# SMARTBALL_v1_2.net
KiCad netlist of a schematic drawn in EAGLE
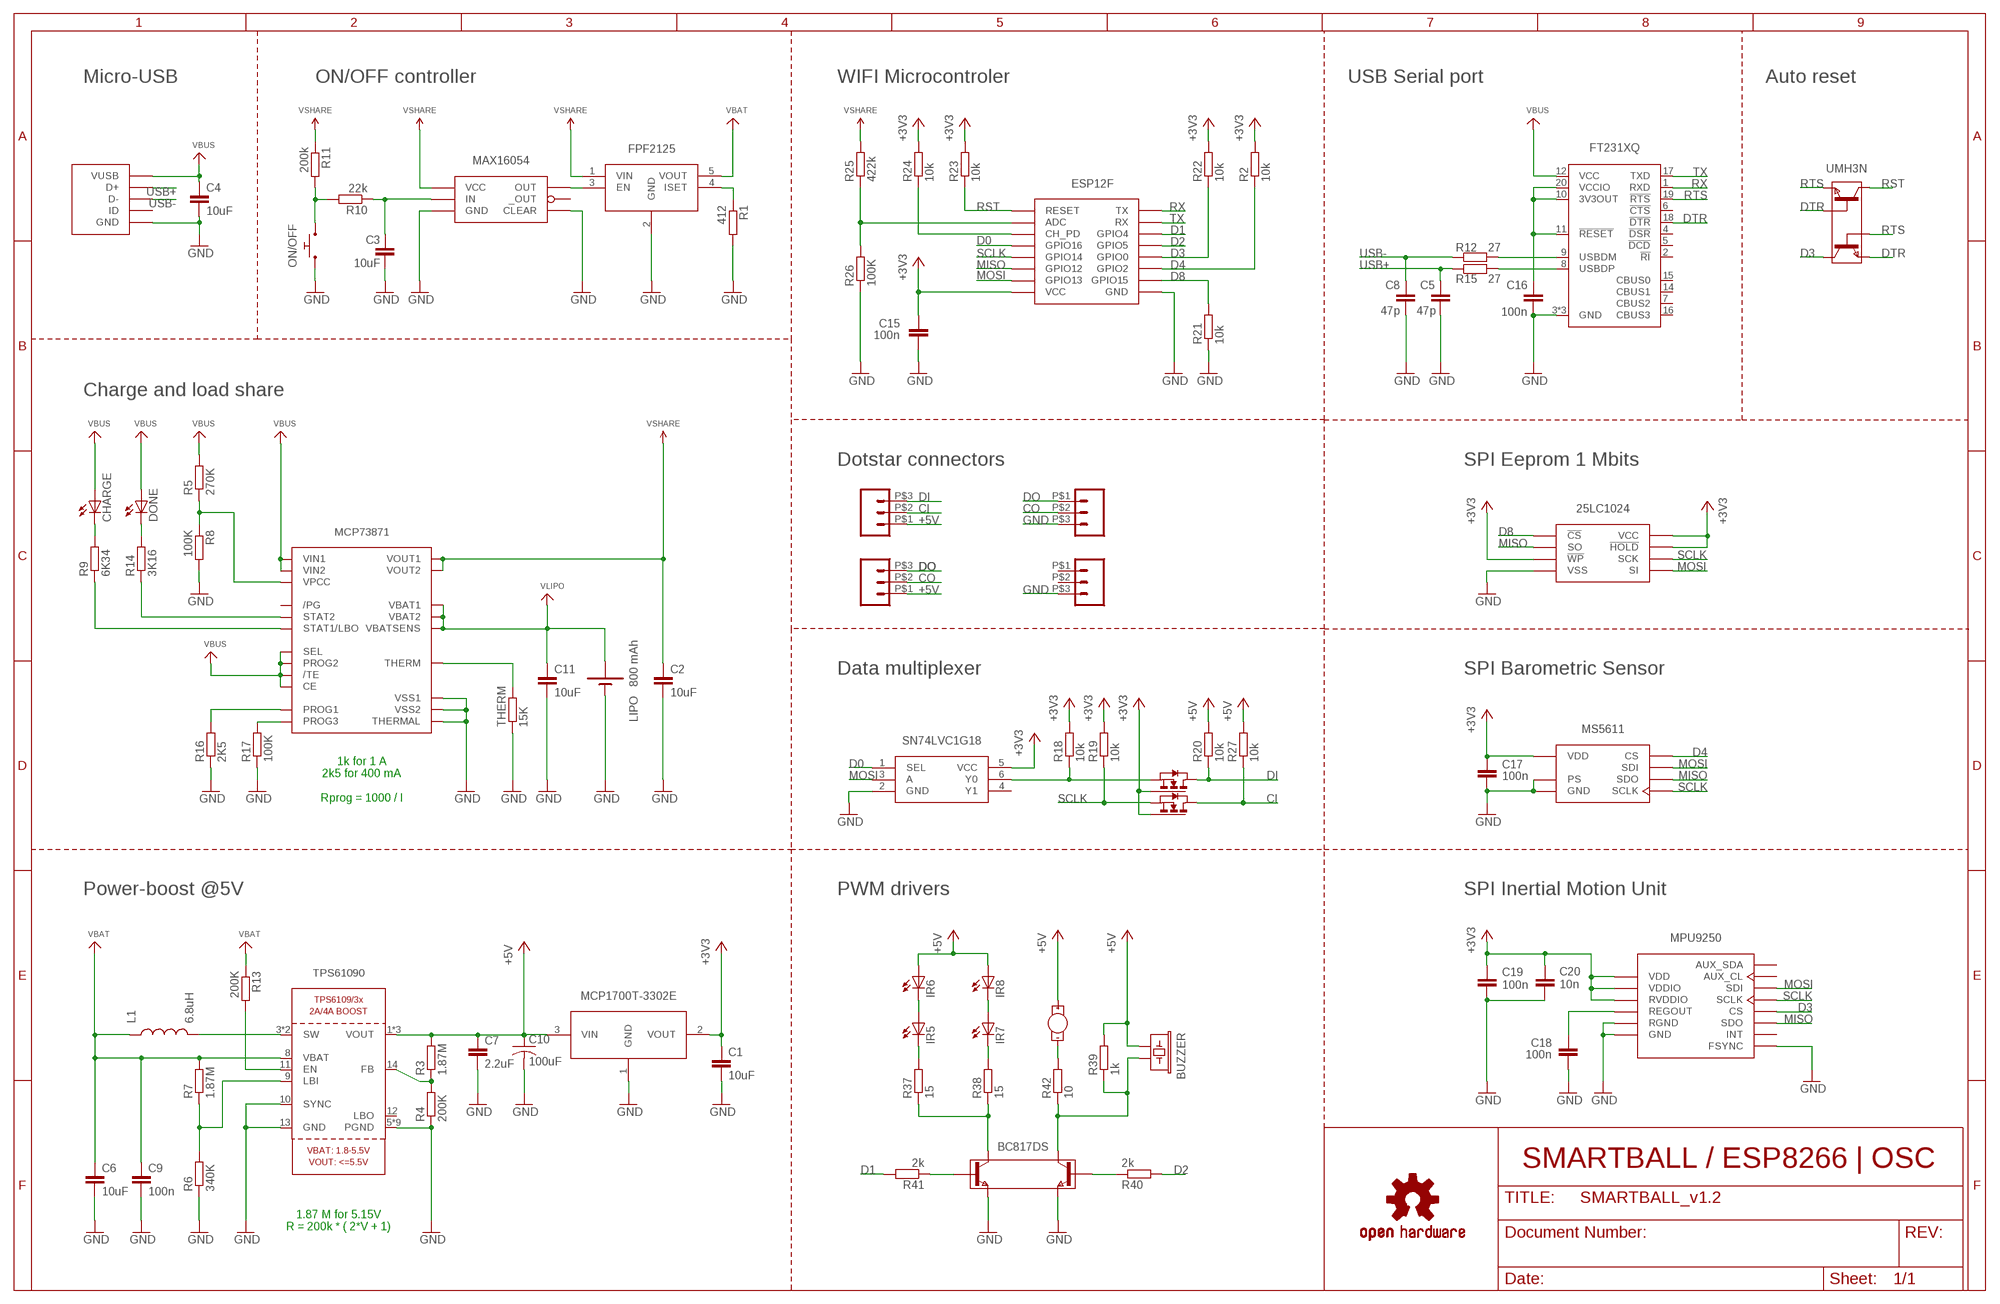
[diagram p0: schematic, sheet 1]

(export (version "E")
  (design (tool "Eeschema 10.0.6"))
  (components
    (comp (ref "BC817DS")
      (value "BC817DS")
      (footprint "eagle-import:SOT457R_PHILIPS")
      (libsource (lib "eagle-import") (part "BC817DS"))
    )
    (comp (ref "BUZZER")
      (value "BUZZER_PKMCS0909E4000-R1")
      (footprint "eagle-import:BUZZER_PKMCS0909E4000-R1")
      (libsource (lib "eagle-import") (part "BUZZER_PKMCS0909E4000-R1"))
    )
    (comp (ref "C1")
      (value "10uF")
      (footprint "eagle-import:C0603K")
      (libsource (lib "eagle-import") (part "C-EUC0603K"))
    )
    (comp (ref "C2")
      (value "10uF")
      (footprint "eagle-import:C0603K")
      (libsource (lib "eagle-import") (part "C-EUC0603K"))
    )
    (comp (ref "C3")
      (value "10uF")
      (footprint "eagle-import:C0603K")
      (libsource (lib "eagle-import") (part "C-EUC0603K"))
    )
    (comp (ref "C4")
      (value "10uF")
      (footprint "eagle-import:C0603K")
      (libsource (lib "eagle-import") (part "C-EUC0603K"))
    )
    (comp (ref "C5")
      (value "47p")
      (footprint "eagle-import:C0603K")
      (libsource (lib "eagle-import") (part "C-EUC0603K"))
    )
    (comp (ref "C6")
      (value "10uF")
      (footprint "eagle-import:C0603K")
      (libsource (lib "eagle-import") (part "C-EUC0603K"))
    )
    (comp (ref "C7")
      (value "2.2uF")
      (footprint "eagle-import:C0603K")
      (libsource (lib "eagle-import") (part "C-EUC0603K"))
    )
    (comp (ref "C8")
      (value "47p")
      (footprint "eagle-import:C0603K")
      (libsource (lib "eagle-import") (part "C-EUC0603K"))
    )
    (comp (ref "C9")
      (value "100n")
      (footprint "eagle-import:C0603K")
      (libsource (lib "eagle-import") (part "C-EUC0603K"))
    )
    (comp (ref "C10")
      (value "100uF")
      (footprint "eagle-import:C1210")
      (libsource (lib "eagle-import") (part "C-USC1210"))
    )
    (comp (ref "C11")
      (value "10uF")
      (footprint "eagle-import:C0603K")
      (libsource (lib "eagle-import") (part "C-EUC0603K"))
    )
    (comp (ref "C15")
      (value "100n")
      (footprint "eagle-import:C0603K")
      (libsource (lib "eagle-import") (part "C-EUC0603K"))
    )
    (comp (ref "C16")
      (value "100n")
      (footprint "eagle-import:C0603K")
      (libsource (lib "eagle-import") (part "C-EUC0603K"))
    )
    (comp (ref "C17")
      (value "100n")
      (footprint "eagle-import:C0603K")
      (libsource (lib "eagle-import") (part "C-EUC0603K"))
    )
    (comp (ref "C18")
      (value "100n")
      (footprint "eagle-import:C0603K")
      (libsource (lib "eagle-import") (part "C-EUC0603K"))
    )
    (comp (ref "C19")
      (value "100n")
      (footprint "eagle-import:C0603K")
      (libsource (lib "eagle-import") (part "C-EUC0603K"))
    )
    (comp (ref "C20")
      (value "10n")
      (footprint "eagle-import:C0603K")
      (libsource (lib "eagle-import") (part "C-EUC0603K"))
    )
    (comp (ref "CHARGE")
      (value "KINGBRIGHT_16X08")
      (footprint "eagle-import:KINGBRIGHT_16X08")
      (libsource (lib "eagle-import") (part "KINGBRIGHT_16X08"))
    )
    (comp (ref "DONE")
      (value "KINGBRIGHT_16X08")
      (footprint "eagle-import:KINGBRIGHT_16X08")
      (libsource (lib "eagle-import") (part "KINGBRIGHT_16X08"))
    )
    (comp (ref "ESP12F")
      (value "ESP12")
      (footprint "eagle-import:ESP12")
      (libsource (lib "eagle-import") (part "ESP12"))
    )
    (comp (ref "FT231XQ")
      (value "FT231X")
      (footprint "eagle-import:QFN20")
      (libsource (lib "eagle-import") (part "FT231X"))
    )
    (comp (ref "IR5")
      (value "LED-SFH4050")
      (footprint "eagle-import:SFH4050")
      (libsource (lib "eagle-import") (part "LED-SFH4050"))
    )
    (comp (ref "IR6")
      (value "LED-SFH4050")
      (footprint "eagle-import:SFH4050")
      (libsource (lib "eagle-import") (part "LED-SFH4050"))
    )
    (comp (ref "IR7")
      (value "LED-SFH4050")
      (footprint "eagle-import:SFH4050")
      (libsource (lib "eagle-import") (part "LED-SFH4050"))
    )
    (comp (ref "IR8")
      (value "LED-SFH4050")
      (footprint "eagle-import:SFH4050")
      (libsource (lib "eagle-import") (part "LED-SFH4050"))
    )
    (comp (ref "L1")
      (value "6.8uH")
      (footprint "eagle-import:ASPIAIG-S4035")
      (libsource (lib "eagle-import") (part "ASPIAIG-S4035"))
    )
    (comp (ref "LIPO")
      (value "BATTERY_CONNECTOR")
      (footprint "eagle-import:MOTOR_CONNECTOR")
      (libsource (lib "eagle-import") (part "BATTERY_CONNECTOR"))
    )
    (comp (ref "LOGO1")
      (value "OSHW-LOGOL")
      (footprint "eagle-import:OSHW-LOGO-L")
      (libsource (lib "eagle-import") (part "OSHW-LOGOL"))
    )
    (comp (ref "MCP73871")
      (value "MCP73871")
      (footprint "eagle-import:QFN20_4MM")
      (libsource (lib "eagle-import") (part "MCP73871"))
    )
    (comp (ref "MOTOR")
      (value "MOTOR_CONNECTOR")
      (footprint "eagle-import:MOTOR_CONNECTOR")
      (libsource (lib "eagle-import") (part "MOTOR_CONNECTOR"))
    )
    (comp (ref "ON/OFF")
      (value "B3U-3000P-B")
      (footprint "eagle-import:B3U-3000P-B")
      (libsource (lib "eagle-import") (part "B3U-3000P-B"))
    )
    (comp (ref "R1")
      (value "412")
      (footprint "eagle-import:R0402")
      (libsource (lib "eagle-import") (part "R-EU_R0402"))
    )
    (comp (ref "R2")
      (value "10k")
      (footprint "eagle-import:R0402")
      (libsource (lib "eagle-import") (part "R-EU_R0402"))
    )
    (comp (ref "R3")
      (value "1.87M")
      (footprint "eagle-import:R0402")
      (libsource (lib "eagle-import") (part "R-EU_R0402"))
    )
    (comp (ref "R4")
      (value "200K")
      (footprint "eagle-import:R0402")
      (libsource (lib "eagle-import") (part "R-EU_R0402"))
    )
    (comp (ref "R5")
      (value "270K")
      (footprint "eagle-import:R0402")
      (libsource (lib "eagle-import") (part "R-EU_R0402"))
    )
    (comp (ref "R6")
      (value "340K")
      (footprint "eagle-import:R0402")
      (libsource (lib "eagle-import") (part "R-EU_R0402"))
    )
    (comp (ref "R7")
      (value "1.87M")
      (footprint "eagle-import:R0402")
      (libsource (lib "eagle-import") (part "R-EU_R0402"))
    )
    (comp (ref "R8")
      (value "100K")
      (footprint "eagle-import:R0402")
      (libsource (lib "eagle-import") (part "R-EU_R0402"))
    )
    (comp (ref "R9")
      (value "6K34")
      (footprint "eagle-import:R0402")
      (libsource (lib "eagle-import") (part "R-EU_R0402"))
    )
    (comp (ref "R10")
      (value "22k")
      (footprint "eagle-import:R0402")
      (libsource (lib "eagle-import") (part "R-EU_R0402"))
    )
    (comp (ref "R11")
      (value "200k")
      (footprint "eagle-import:R0402")
      (libsource (lib "eagle-import") (part "R-EU_R0402"))
    )
    (comp (ref "R12")
      (value "27")
      (footprint "eagle-import:R0402")
      (libsource (lib "eagle-import") (part "R-EU_R0402"))
    )
    (comp (ref "R13")
      (value "200K")
      (footprint "eagle-import:R0402")
      (libsource (lib "eagle-import") (part "R-EU_R0402"))
    )
    (comp (ref "R14")
      (value "3K16")
      (footprint "eagle-import:R0402")
      (libsource (lib "eagle-import") (part "R-EU_R0402"))
    )
    (comp (ref "R15")
      (value "27")
      (footprint "eagle-import:R0402")
      (libsource (lib "eagle-import") (part "R-EU_R0402"))
    )
    (comp (ref "R16")
      (value "2K5")
      (footprint "eagle-import:R0402")
      (libsource (lib "eagle-import") (part "R-EU_R0402"))
    )
    (comp (ref "R17")
      (value "100K")
      (footprint "eagle-import:R0402")
      (libsource (lib "eagle-import") (part "R-EU_R0402"))
    )
    (comp (ref "R18")
      (value "10k")
      (footprint "eagle-import:R0402")
      (libsource (lib "eagle-import") (part "R-EU_R0402"))
    )
    (comp (ref "R19")
      (value "10k")
      (footprint "eagle-import:R0402")
      (libsource (lib "eagle-import") (part "R-EU_R0402"))
    )
    (comp (ref "R20")
      (value "10k")
      (footprint "eagle-import:R0402")
      (libsource (lib "eagle-import") (part "R-EU_R0402"))
    )
    (comp (ref "R21")
      (value "10k")
      (footprint "eagle-import:R0402")
      (libsource (lib "eagle-import") (part "R-EU_R0402"))
    )
    (comp (ref "R22")
      (value "10k")
      (footprint "eagle-import:R0402")
      (libsource (lib "eagle-import") (part "R-EU_R0402"))
    )
    (comp (ref "R23")
      (value "10k")
      (footprint "eagle-import:R0402")
      (libsource (lib "eagle-import") (part "R-EU_R0402"))
    )
    (comp (ref "R24")
      (value "10k")
      (footprint "eagle-import:R0402")
      (libsource (lib "eagle-import") (part "R-EU_R0402"))
    )
    (comp (ref "R25")
      (value "422k")
      (footprint "eagle-import:R0402")
      (libsource (lib "eagle-import") (part "R-EU_R0402"))
    )
    (comp (ref "R26")
      (value "100K")
      (footprint "eagle-import:R0402")
      (libsource (lib "eagle-import") (part "R-EU_R0402"))
    )
    (comp (ref "R27")
      (value "10k")
      (footprint "eagle-import:R0402")
      (libsource (lib "eagle-import") (part "R-EU_R0402"))
    )
    (comp (ref "R37")
      (value "15")
      (footprint "eagle-import:R0402")
      (libsource (lib "eagle-import") (part "R-EU_R0402"))
    )
    (comp (ref "R38")
      (value "15")
      (footprint "eagle-import:R0402")
      (libsource (lib "eagle-import") (part "R-EU_R0402"))
    )
    (comp (ref "R39")
      (value "1k")
      (footprint "eagle-import:R0402")
      (libsource (lib "eagle-import") (part "R-EU_R0402"))
    )
    (comp (ref "R40")
      (value "2k")
      (footprint "eagle-import:R0402")
      (libsource (lib "eagle-import") (part "R-EU_R0402"))
    )
    (comp (ref "R41")
      (value "2k")
      (footprint "eagle-import:R0402")
      (libsource (lib "eagle-import") (part "R-EU_R0402"))
    )
    (comp (ref "R42")
      (value "10")
      (footprint "eagle-import:R0402")
      (libsource (lib "eagle-import") (part "R-EU_R0402"))
    )
    (comp (ref "THERM")
      (value "15K")
      (footprint "eagle-import:R0402")
      (libsource (lib "eagle-import") (part "R-EU_R0402"))
    )
    (comp (ref "TPS61090")
      (value "TPS61090RSAR")
      (footprint "eagle-import:PVQFN-16")
      (libsource (lib "eagle-import") (part "VREG_TPS6103X"))
    )
    (comp (ref "U$1")
      (value "MOLEX-USB")
      (footprint "eagle-import:MOLEX-USB")
      (libsource (lib "eagle-import") (part "MOLEX-USB"))
    )
    (comp (ref "U$2")
      (value "FPF2125")
      (footprint "eagle-import:SOT23-5")
      (libsource (lib "eagle-import") (part "FPF2125"))
    )
    (comp (ref "U$3")
      (value "MCP1700T")
      (footprint "eagle-import:SOT23-3")
      (libsource (lib "eagle-import") (part "MCP1700T"))
    )
    (comp (ref "U$5")
      (value "CONN_03_SMD")
      (footprint "eagle-import:CONN03_SMD")
      (libsource (lib "eagle-import") (part "CONN_03_SMD"))
    )
    (comp (ref "U$6")
      (value "CONN_03_SMD")
      (footprint "eagle-import:CONN03_SMD")
      (libsource (lib "eagle-import") (part "CONN_03_SMD"))
    )
    (comp (ref "U$12")
      (value "MAX16054")
      (footprint "eagle-import:TSOT23-6")
      (libsource (lib "eagle-import") (part "MAX16054"))
    )
    (comp (ref "U$14")
      (value "CONN_03_SMD")
      (footprint "eagle-import:CONN03_SMD")
      (libsource (lib "eagle-import") (part "CONN_03_SMD"))
    )
    (comp (ref "U$15")
      (value "CONN_03_SMD")
      (footprint "eagle-import:CONN03_SMD")
      (libsource (lib "eagle-import") (part "CONN_03_SMD"))
    )
    (comp (ref "U$16")
      (value "25LC1024DFN-S")
      (footprint "eagle-import:DFN-S")
      (libsource (lib "eagle-import") (part "25LC1024DFN-S"))
    )
    (comp (ref "U$17")
      (value "MS5611")
      (footprint "eagle-import:MS5611-QFN")
      (libsource (lib "eagle-import") (part "MS5611"))
    )
    (comp (ref "U$20")
      (value "SN74LVC1G18")
      (footprint "eagle-import:DCK_R-PDSO-G6")
      (libsource (lib "eagle-import") (part "SN74LVC1G18"))
    )
    (comp (ref "U$21")
      (value "MPU-9250QFN24G")
      (footprint "eagle-import:QFN24G-0.4-3X3MM")
      (libsource (lib "eagle-import") (part "MPU-9250QFN24G"))
    )
    (comp (ref "U$22")
      (value "2N7002PS")
      (footprint "eagle-import:SOT363_PHILIPS")
      (libsource (lib "eagle-import") (part "2N7002PS"))
    )
    (comp (ref "UMH3N")
      (value "UMH3N")
      (footprint "eagle-import:SOT363_PHILIPS")
      (libsource (lib "eagle-import") (part "UMH3N"))
    )
  )
  (nets
    (net (code "1") (name "+3V3") (class "Default")
      (node (ref "C1") (pin "1") (pinfunction "1_1") (pintype "passive"))
      (node (ref "C15") (pin "1") (pinfunction "1_1") (pintype "passive"))
      (node (ref "C17") (pin "1") (pinfunction "1_1") (pintype "passive"))
      (node (ref "C19") (pin "1") (pinfunction "1_1") (pintype "passive"))
      (node (ref "C20") (pin "2") (pinfunction "2_2") (pintype "passive"))
      (node (ref "ESP12F") (pin "VCC") (pinfunction "VCC_VCC") (pintype "bidirectional"))
      (node (ref "R18") (pin "2") (pinfunction "2_2") (pintype "passive"))
      (node (ref "R19") (pin "2") (pinfunction "2_2") (pintype "passive"))
      (node (ref "R2") (pin "2") (pinfunction "2_2") (pintype "passive"))
      (node (ref "R22") (pin "2") (pinfunction "2_2") (pintype "passive"))
      (node (ref "R23") (pin "2") (pinfunction "2_2") (pintype "passive"))
      (node (ref "R24") (pin "2") (pinfunction "2_2") (pintype "passive"))
      (node (ref "U$16") (pin "3") (pinfunction "~{WP}_3") (pintype "bidirectional"))
      (node (ref "U$16") (pin "7") (pinfunction "~{HOLD}_7") (pintype "bidirectional"))
      (node (ref "U$16") (pin "8") (pinfunction "VCC_8") (pintype "bidirectional"))
      (node (ref "U$17") (pin "P$1") (pinfunction "VDD_P$1") (pintype "power_in"))
      (node (ref "U$20") (pin "5") (pinfunction "VCC_5") (pintype "bidirectional"))
      (node (ref "U$21") (pin "1") (pinfunction "RVDDIO_1") (pintype "bidirectional"))
      (node (ref "U$21") (pin "13") (pinfunction "VDD_13") (pintype "bidirectional"))
      (node (ref "U$21") (pin "8") (pinfunction "VDDIO_8") (pintype "bidirectional"))
      (node (ref "U$22") (pin "2") (pinfunction "G1_2") (pintype "passive"))
      (node (ref "U$22") (pin "5") (pinfunction "G2_5") (pintype "passive"))
      (node (ref "U$3") (pin "2") (pinfunction "VOUT_2") (pintype "bidirectional"))
    )
    (net (code "2") (name "+5V") (class "Default")
      (node (ref "BUZZER") (pin "P$1") (pinfunction "1_P$1") (pintype "passive"))
      (node (ref "C10") (pin "1") (pinfunction "1_1") (pintype "passive"))
      (node (ref "C7") (pin "1") (pinfunction "1_1") (pintype "passive"))
      (node (ref "IR6") (pin "P$1") (pinfunction "A_P$1") (pintype "passive"))
      (node (ref "IR8") (pin "P$1") (pinfunction "A_P$1") (pintype "passive"))
      (node (ref "MOTOR") (pin "+") (pinfunction "+_+") (pintype "bidirectional"))
      (node (ref "R20") (pin "2") (pinfunction "2_2") (pintype "passive"))
      (node (ref "R27") (pin "2") (pinfunction "2_2") (pintype "passive"))
      (node (ref "R3") (pin "2") (pinfunction "2_2") (pintype "passive"))
      (node (ref "R39") (pin "2") (pinfunction "2_2") (pintype "passive"))
      (node (ref "TPS61090") (pin "1") (pinfunction "VOUT_1") (pintype "power_in"))
      (node (ref "TPS61090") (pin "15") (pinfunction "VOUT_15") (pintype "power_in"))
      (node (ref "TPS61090") (pin "16") (pinfunction "VOUT_16") (pintype "power_in"))
      (node (ref "U$15") (pin "P$1") (pinfunction "1_P$1") (pintype "passive"))
      (node (ref "U$3") (pin "3") (pinfunction "VIN_3") (pintype "bidirectional"))
      (node (ref "U$5") (pin "P$1") (pinfunction "1_P$1") (pintype "passive"))
    )
    (net (code "3") (name "/CI") (class "Default")
      (node (ref "R27") (pin "1") (pinfunction "1_1") (pintype "passive"))
      (node (ref "U$22") (pin "3") (pinfunction "D2_3") (pintype "passive"))
      (node (ref "U$5") (pin "P$2") (pinfunction "2_P$2") (pintype "passive"))
    )
    (net (code "4") (name "/CO") (class "Default")
      (node (ref "U$15") (pin "P$2") (pinfunction "2_P$2") (pintype "passive"))
      (node (ref "U$6") (pin "P$2") (pinfunction "2_P$2") (pintype "passive"))
    )
    (net (code "5") (name "/D0") (class "Default")
      (node (ref "ESP12F") (pin "GPIO16") (pinfunction "GPIO16_GPIO16") (pintype "bidirectional"))
      (node (ref "U$20") (pin "1") (pinfunction "SEL_1") (pintype "bidirectional"))
    )
    (net (code "6") (name "/D1") (class "Default")
      (node (ref "ESP12F") (pin "GPIO4") (pinfunction "GPIO4_GPIO4") (pintype "bidirectional"))
      (node (ref "R41") (pin "2") (pinfunction "2_2") (pintype "passive"))
    )
    (net (code "7") (name "/D2") (class "Default")
      (node (ref "ESP12F") (pin "GPIO5") (pinfunction "GPIO5_GPIO5") (pintype "bidirectional"))
      (node (ref "R40") (pin "2") (pinfunction "2_2") (pintype "passive"))
    )
    (net (code "8") (name "/D3") (class "Default")
      (node (ref "ESP12F") (pin "GPIO0") (pinfunction "GPIO0_GPIO0") (pintype "bidirectional"))
      (node (ref "R22") (pin "1") (pinfunction "1_1") (pintype "passive"))
      (node (ref "U$21") (pin "22") (pinfunction "CS_22") (pintype "bidirectional"))
      (node (ref "UMH3N") (pin "3") (pinfunction "C2_3") (pintype "passive"))
    )
    (net (code "9") (name "/D4") (class "Default")
      (node (ref "ESP12F") (pin "GPIO2") (pinfunction "GPIO2_GPIO2") (pintype "bidirectional"))
      (node (ref "R2") (pin "1") (pinfunction "1_1") (pintype "passive"))
      (node (ref "U$17") (pin "P$4") (pinfunction "CS_P$4") (pintype "bidirectional"))
      (node (ref "U$17") (pin "P$5") (pinfunction "CS_P$5") (pintype "bidirectional"))
    )
    (net (code "10") (name "/D8") (class "Default")
      (node (ref "ESP12F") (pin "GPIO15") (pinfunction "GPIO15_GPIO15") (pintype "bidirectional"))
      (node (ref "R21") (pin "2") (pinfunction "2_2") (pintype "passive"))
      (node (ref "U$16") (pin "1") (pinfunction "~{CS}_1") (pintype "bidirectional"))
    )
    (net (code "11") (name "/DI") (class "Default")
      (node (ref "R20") (pin "1") (pinfunction "1_1") (pintype "passive"))
      (node (ref "U$22") (pin "6") (pinfunction "D1_6") (pintype "passive"))
      (node (ref "U$5") (pin "P$3") (pinfunction "3_P$3") (pintype "passive"))
    )
    (net (code "12") (name "/DO") (class "Default")
      (node (ref "U$15") (pin "P$3") (pinfunction "3_P$3") (pintype "passive"))
      (node (ref "U$6") (pin "P$1") (pinfunction "1_P$1") (pintype "passive"))
    )
    (net (code "13") (name "/DTR") (class "Default")
      (node (ref "FT231XQ") (pin "18") (pinfunction "~{DTR}_18") (pintype "bidirectional"))
      (node (ref "UMH3N") (pin "2") (pinfunction "B1_2") (pintype "passive"))
      (node (ref "UMH3N") (pin "4") (pinfunction "E2_4") (pintype "passive"))
    )
    (net (code "14") (name "/MISO") (class "Default")
      (node (ref "ESP12F") (pin "GPIO12") (pinfunction "GPIO12_GPIO12") (pintype "bidirectional"))
      (node (ref "U$16") (pin "2") (pinfunction "SO_2") (pintype "bidirectional"))
      (node (ref "U$17") (pin "P$6") (pinfunction "SDO_P$6") (pintype "output"))
      (node (ref "U$21") (pin "9") (pinfunction "SDO_9") (pintype "bidirectional"))
    )
    (net (code "15") (name "/MOSI") (class "Default")
      (node (ref "ESP12F") (pin "GPIO13") (pinfunction "GPIO13_GPIO13") (pintype "bidirectional"))
      (node (ref "U$16") (pin "5") (pinfunction "SI_5") (pintype "bidirectional"))
      (node (ref "U$17") (pin "P$7") (pinfunction "SDI_P$7") (pintype "input"))
      (node (ref "U$20") (pin "3") (pinfunction "A_3") (pintype "bidirectional"))
      (node (ref "U$21") (pin "24") (pinfunction "SDI_24") (pintype "bidirectional"))
    )
    (net (code "16") (name "/RST") (class "Default")
      (node (ref "ESP12F") (pin "RESET") (pinfunction "RESET_RESET") (pintype "bidirectional"))
      (node (ref "R23") (pin "1") (pinfunction "1_1") (pintype "passive"))
      (node (ref "UMH3N") (pin "6") (pinfunction "C1_6") (pintype "passive"))
    )
    (net (code "17") (name "/RTS") (class "Default")
      (node (ref "FT231XQ") (pin "19") (pinfunction "~{RTS}_19") (pintype "bidirectional"))
      (node (ref "UMH3N") (pin "1") (pinfunction "E1_1") (pintype "passive"))
      (node (ref "UMH3N") (pin "5") (pinfunction "B2_5") (pintype "passive"))
    )
    (net (code "18") (name "/RX") (class "Default")
      (node (ref "ESP12F") (pin "TX") (pinfunction "TX_TX") (pintype "bidirectional"))
      (node (ref "FT231XQ") (pin "1") (pinfunction "RXD_1") (pintype "bidirectional"))
    )
    (net (code "19") (name "/SCLK") (class "Default")
      (node (ref "ESP12F") (pin "GPIO14") (pinfunction "GPIO14_GPIO14") (pintype "bidirectional"))
      (node (ref "R19") (pin "1") (pinfunction "1_1") (pintype "passive"))
      (node (ref "U$16") (pin "6") (pinfunction "SCK_6") (pintype "bidirectional"))
      (node (ref "U$17") (pin "P$8") (pinfunction "SCLK_P$8") (pintype "input"))
      (node (ref "U$21") (pin "23") (pinfunction "SCLK_23") (pintype "bidirectional"))
      (node (ref "U$22") (pin "4") (pinfunction "S2_4") (pintype "passive"))
    )
    (net (code "20") (name "/TX") (class "Default")
      (node (ref "ESP12F") (pin "RX") (pinfunction "RX_RX") (pintype "bidirectional"))
      (node (ref "FT231XQ") (pin "17") (pinfunction "TXD_17") (pintype "bidirectional"))
    )
    (net (code "21") (name "/USB+") (class "Default")
      (node (ref "C5") (pin "1") (pinfunction "1_1") (pintype "passive"))
      (node (ref "R15") (pin "1") (pinfunction "1_1") (pintype "passive"))
      (node (ref "U$1") (pin "D+") (pinfunction "D+_D+") (pintype "bidirectional"))
    )
    (net (code "22") (name "/USB-") (class "Default")
      (node (ref "C8") (pin "1") (pinfunction "1_1") (pintype "passive"))
      (node (ref "R12") (pin "1") (pinfunction "1_1") (pintype "passive"))
      (node (ref "U$1") (pin "D-") (pinfunction "D-_D-") (pintype "bidirectional"))
    )
    (net (code "23") (name "GND") (class "Default")
      (node (ref "BC817DS") (pin "1") (pinfunction "E1_1") (pintype "passive"))
      (node (ref "BC817DS") (pin "4") (pinfunction "E2_4") (pintype "passive"))
      (node (ref "C1") (pin "2") (pinfunction "2_2") (pintype "passive"))
      (node (ref "C10") (pin "2") (pinfunction "2_2") (pintype "passive"))
      (node (ref "C11") (pin "2") (pinfunction "2_2") (pintype "passive"))
      (node (ref "C15") (pin "2") (pinfunction "2_2") (pintype "passive"))
      (node (ref "C16") (pin "2") (pinfunction "2_2") (pintype "passive"))
      (node (ref "C17") (pin "2") (pinfunction "2_2") (pintype "passive"))
      (node (ref "C18") (pin "2") (pinfunction "2_2") (pintype "passive"))
      (node (ref "C19") (pin "2") (pinfunction "2_2") (pintype "passive"))
      (node (ref "C2") (pin "2") (pinfunction "2_2") (pintype "passive"))
      (node (ref "C20") (pin "1") (pinfunction "1_1") (pintype "passive"))
      (node (ref "C3") (pin "2") (pinfunction "2_2") (pintype "passive"))
      (node (ref "C4") (pin "2") (pinfunction "2_2") (pintype "passive"))
      (node (ref "C5") (pin "2") (pinfunction "2_2") (pintype "passive"))
      (node (ref "C6") (pin "2") (pinfunction "2_2") (pintype "passive"))
      (node (ref "C7") (pin "2") (pinfunction "2_2") (pintype "passive"))
      (node (ref "C8") (pin "2") (pinfunction "2_2") (pintype "passive"))
      (node (ref "C9") (pin "2") (pinfunction "2_2") (pintype "passive"))
      (node (ref "ESP12F") (pin "GND") (pinfunction "GND_GND") (pintype "bidirectional"))
      (node (ref "FT231XQ") (pin "13") (pinfunction "GND_13") (pintype "bidirectional"))
      (node (ref "FT231XQ") (pin "3") (pinfunction "GND_3") (pintype "bidirectional"))
      (node (ref "FT231XQ") (pin "EXP") (pinfunction "GND_EXP") (pintype "bidirectional"))
      (node (ref "LIPO") (pin "-") (pinfunction "-_-") (pintype "power_in"))
      (node (ref "MCP73871") (pin "P$10") (pinfunction "VSS1_P$10") (pintype "bidirectional"))
      (node (ref "MCP73871") (pin "P$11") (pinfunction "VSS2_P$11") (pintype "bidirectional"))
      (node (ref "MCP73871") (pin "P$21") (pinfunction "THERMAL_P$21") (pintype "bidirectional"))
      (node (ref "ON/OFF") (pin "P$1") (pinfunction "1_P$1") (pintype "passive"))
      (node (ref "R1") (pin "2") (pinfunction "2_2") (pintype "passive"))
      (node (ref "R16") (pin "1") (pinfunction "1_1") (pintype "passive"))
      (node (ref "R17") (pin "1") (pinfunction "1_1") (pintype "passive"))
      (node (ref "R21") (pin "1") (pinfunction "1_1") (pintype "passive"))
      (node (ref "R26") (pin "1") (pinfunction "1_1") (pintype "passive"))
      (node (ref "R4") (pin "1") (pinfunction "1_1") (pintype "passive"))
      (node (ref "R6") (pin "1") (pinfunction "1_1") (pintype "passive"))
      (node (ref "R8") (pin "2") (pinfunction "2_2") (pintype "passive"))
      (node (ref "THERM") (pin "1") (pinfunction "1_1") (pintype "passive"))
      (node (ref "TPS61090") (pin "10") (pinfunction "SYNC_10") (pintype "input"))
      (node (ref "TPS61090") (pin "13") (pinfunction "GND_13") (pintype "power_in"))
      (node (ref "TPS61090") (pin "5") (pinfunction "PGND_5") (pintype "power_in"))
      (node (ref "TPS61090") (pin "6") (pinfunction "PGND_6") (pintype "power_in"))
      (node (ref "TPS61090") (pin "7") (pinfunction "PGND_7") (pintype "power_in"))
      (node (ref "TPS61090") (pin "P$18") (pinfunction "PGND_P$18") (pintype "power_in"))
      (node (ref "TPS61090") (pin "P$19") (pinfunction "PGND_P$19") (pintype "power_in"))
      (node (ref "TPS61090") (pin "P$20") (pinfunction "PGND_P$20") (pintype "power_in"))
      (node (ref "TPS61090") (pin "P$21") (pinfunction "PGND_P$21") (pintype "power_in"))
      (node (ref "TPS61090") (pin "P$22") (pinfunction "PGND_P$22") (pintype "power_in"))
      (node (ref "TPS61090") (pin "THERMAL") (pinfunction "PGND_THERMAL") (pintype "power_in"))
      (node (ref "U$1") (pin "GND") (pinfunction "GND_GND") (pintype "bidirectional"))
      (node (ref "U$1") (pin "P$1") (pinfunction "GND_P$1") (pintype "bidirectional"))
      (node (ref "U$1") (pin "P$11") (pinfunction "GND_P$11") (pintype "bidirectional"))
      (node (ref "U$1") (pin "SHELL1") (pinfunction "GND_SHELL1") (pintype "bidirectional"))
      (node (ref "U$1") (pin "SHELL2") (pinfunction "GND_SHELL2") (pintype "bidirectional"))
      (node (ref "U$1") (pin "SHELL5") (pinfunction "GND_SHELL5") (pintype "bidirectional"))
      (node (ref "U$1") (pin "SHELL6") (pinfunction "GND_SHELL6") (pintype "bidirectional"))
      (node (ref "U$12") (pin "CLEAR") (pinfunction "CLEAR_CLEAR") (pintype "bidirectional"))
      (node (ref "U$12") (pin "GND") (pinfunction "GND_GND") (pintype "bidirectional"))
      (node (ref "U$14") (pin "P$3") (pinfunction "3_P$3") (pintype "passive"))
      (node (ref "U$16") (pin "4") (pinfunction "VSS_4") (pintype "bidirectional"))
      (node (ref "U$17") (pin "P$2") (pinfunction "PS_P$2") (pintype "input"))
      (node (ref "U$17") (pin "P$3") (pinfunction "GND_P$3") (pintype "power_in"))
      (node (ref "U$2") (pin "2") (pinfunction "GND_2") (pintype "bidirectional"))
      (node (ref "U$20") (pin "2") (pinfunction "GND_2") (pintype "bidirectional"))
      (node (ref "U$21") (pin "11") (pinfunction "FSYNC_11") (pintype "bidirectional"))
      (node (ref "U$21") (pin "18") (pinfunction "GND_18") (pintype "bidirectional"))
      (node (ref "U$21") (pin "20") (pinfunction "RGND_20") (pintype "bidirectional"))
      (node (ref "U$3") (pin "1") (pinfunction "GND_1") (pintype "bidirectional"))
      (node (ref "U$6") (pin "P$3") (pinfunction "3_P$3") (pintype "passive"))
    )
    (net (code "24") (name "Net-(BC817DS-B1)") (class "Default")
      (node (ref "BC817DS") (pin "2") (pinfunction "B1_2") (pintype "passive"))
      (node (ref "R40") (pin "1") (pinfunction "1_1") (pintype "passive"))
    )
    (net (code "25") (name "Net-(BC817DS-B2)") (class "Default")
      (node (ref "BC817DS") (pin "5") (pinfunction "B2_5") (pintype "passive"))
      (node (ref "R41") (pin "1") (pinfunction "1_1") (pintype "passive"))
    )
    (net (code "26") (name "Net-(BC817DS-C1)") (class "Default")
      (node (ref "BC817DS") (pin "6") (pinfunction "C1_6") (pintype "passive"))
      (node (ref "BUZZER") (pin "P$2") (pinfunction "2_P$2") (pintype "passive"))
      (node (ref "R39") (pin "1") (pinfunction "1_1") (pintype "passive"))
      (node (ref "R42") (pin "1") (pinfunction "1_1") (pintype "passive"))
    )
    (net (code "27") (name "Net-(BC817DS-C2)") (class "Default")
      (node (ref "BC817DS") (pin "3") (pinfunction "C2_3") (pintype "passive"))
      (node (ref "R37") (pin "1") (pinfunction "1_1") (pintype "passive"))
      (node (ref "R38") (pin "1") (pinfunction "1_1") (pintype "passive"))
    )
    (net (code "28") (name "Net-(C3-Pad1)") (class "Default")
      (node (ref "C3") (pin "1") (pinfunction "1_1") (pintype "passive"))
      (node (ref "R10") (pin "1") (pinfunction "1_1") (pintype "passive"))
      (node (ref "U$12") (pin "IN") (pinfunction "IN_IN") (pintype "bidirectional"))
    )
    (net (code "29") (name "Net-(CHARGE-C)") (class "Default")
      (node (ref "CHARGE") (pin "CATHODE") (pinfunction "C_CATHODE") (pintype "passive"))
      (node (ref "R9") (pin "2") (pinfunction "2_2") (pintype "passive"))
    )
    (net (code "30") (name "Net-(DONE-C)") (class "Default")
      (node (ref "DONE") (pin "CATHODE") (pinfunction "C_CATHODE") (pintype "passive"))
      (node (ref "R14") (pin "2") (pinfunction "2_2") (pintype "passive"))
    )
    (net (code "31") (name "Net-(ESP12F-PadADC)") (class "Default")
      (node (ref "ESP12F") (pin "ADC") (pinfunction "ADC_ADC") (pintype "bidirectional"))
      (node (ref "R25") (pin "1") (pinfunction "1_1") (pintype "passive"))
      (node (ref "R26") (pin "2") (pinfunction "2_2") (pintype "passive"))
    )
    (net (code "32") (name "Net-(ESP12F-PadCH_PD)") (class "Default")
      (node (ref "ESP12F") (pin "CH_PD") (pinfunction "CH_PD_CH_PD") (pintype "bidirectional"))
      (node (ref "R24") (pin "1") (pinfunction "1_1") (pintype "passive"))
    )
    (net (code "33") (name "Net-(FT231XQ-3V3OUT)") (class "Default")
      (node (ref "C16") (pin "1") (pinfunction "1_1") (pintype "passive"))
      (node (ref "FT231XQ") (pin "10") (pinfunction "3V3OUT_10") (pintype "bidirectional"))
      (node (ref "FT231XQ") (pin "11") (pinfunction "~{RESET}_11") (pintype "bidirectional"))
      (node (ref "FT231XQ") (pin "20") (pinfunction "VCCIO_20") (pintype "bidirectional"))
    )
    (net (code "34") (name "Net-(FT231XQ-USBDM)") (class "Default")
      (node (ref "FT231XQ") (pin "9") (pinfunction "USBDM_9") (pintype "bidirectional"))
      (node (ref "R12") (pin "2") (pinfunction "2_2") (pintype "passive"))
    )
    (net (code "35") (name "Net-(FT231XQ-USBDP)") (class "Default")
      (node (ref "FT231XQ") (pin "8") (pinfunction "USBDP_8") (pintype "bidirectional"))
      (node (ref "R15") (pin "2") (pinfunction "2_2") (pintype "passive"))
    )
    (net (code "36") (name "Net-(IR5-A)") (class "Default")
      (node (ref "IR5") (pin "P$1") (pinfunction "A_P$1") (pintype "passive"))
      (node (ref "IR6") (pin "P$2") (pinfunction "C_P$2") (pintype "passive"))
    )
    (net (code "37") (name "Net-(IR5-C)") (class "Default")
      (node (ref "IR5") (pin "P$2") (pinfunction "C_P$2") (pintype "passive"))
      (node (ref "R37") (pin "2") (pinfunction "2_2") (pintype "passive"))
    )
    (net (code "38") (name "Net-(IR7-A)") (class "Default")
      (node (ref "IR7") (pin "P$1") (pinfunction "A_P$1") (pintype "passive"))
      (node (ref "IR8") (pin "P$2") (pinfunction "C_P$2") (pintype "passive"))
    )
    (net (code "39") (name "Net-(IR7-C)") (class "Default")
      (node (ref "IR7") (pin "P$2") (pinfunction "C_P$2") (pintype "passive"))
      (node (ref "R38") (pin "2") (pinfunction "2_2") (pintype "passive"))
    )
    (net (code "40") (name "Net-(L1-2)") (class "Default")
      (node (ref "L1") (pin "P$2") (pinfunction "2_P$2") (pintype "passive"))
      (node (ref "TPS61090") (pin "3") (pinfunction "SW_3") (pintype "input"))
      (node (ref "TPS61090") (pin "4") (pinfunction "SW_4") (pintype "input"))
    )
    (net (code "41") (name "Net-(MCP73871-PROG1)") (class "Default")
      (node (ref "MCP73871") (pin "P$13") (pinfunction "PROG1_P$13") (pintype "bidirectional"))
      (node (ref "R16") (pin "2") (pinfunction "2_2") (pintype "passive"))
    )
    (net (code "42") (name "Net-(MCP73871-PROG3)") (class "Default")
      (node (ref "MCP73871") (pin "P$12") (pinfunction "PROG3_P$12") (pintype "bidirectional"))
      (node (ref "R17") (pin "2") (pinfunction "2_2") (pintype "passive"))
    )
    (net (code "43") (name "Net-(MCP73871-STAT1{slash}LBO)") (class "Default")
      (node (ref "MCP73871") (pin "P$8") (pinfunction "STAT1/LBO_P$8") (pintype "bidirectional"))
      (node (ref "R9") (pin "1") (pinfunction "1_1") (pintype "passive"))
    )
    (net (code "44") (name "Net-(MCP73871-STAT2)") (class "Default")
      (node (ref "MCP73871") (pin "P$7") (pinfunction "STAT2_P$7") (pintype "bidirectional"))
      (node (ref "R14") (pin "1") (pinfunction "1_1") (pintype "passive"))
    )
    (net (code "45") (name "Net-(MCP73871-THERM)") (class "Default")
      (node (ref "MCP73871") (pin "P$5") (pinfunction "THERM_P$5") (pintype "bidirectional"))
      (node (ref "THERM") (pin "2") (pinfunction "2_2") (pintype "passive"))
    )
    (net (code "46") (name "Net-(MCP73871-VPCC)") (class "Default")
      (node (ref "MCP73871") (pin "P$2") (pinfunction "VPCC_P$2") (pintype "bidirectional"))
      (node (ref "R5") (pin "1") (pinfunction "1_1") (pintype "passive"))
      (node (ref "R8") (pin "1") (pinfunction "1_1") (pintype "passive"))
    )
    (net (code "47") (name "Net-(MOTOR-Pad-)") (class "Default")
      (node (ref "MOTOR") (pin "-") (pinfunction "-_-") (pintype "bidirectional"))
      (node (ref "R42") (pin "2") (pinfunction "2_2") (pintype "passive"))
    )
    (net (code "48") (name "Net-(ON/OFF-2)") (class "Default")
      (node (ref "ON/OFF") (pin "P$2") (pinfunction "2_P$2") (pintype "passive"))
      (node (ref "R10") (pin "2") (pinfunction "2_2") (pintype "passive"))
      (node (ref "R11") (pin "2") (pinfunction "2_2") (pintype "passive"))
    )
    (net (code "49") (name "Net-(TPS61090-EN)") (class "Default")
      (node (ref "R13") (pin "2") (pinfunction "2_2") (pintype "passive"))
      (node (ref "TPS61090") (pin "11") (pinfunction "EN_11") (pintype "input"))
    )
    (net (code "50") (name "Net-(TPS61090-FB)") (class "Default")
      (node (ref "R3") (pin "1") (pinfunction "1_1") (pintype "passive"))
      (node (ref "R4") (pin "2") (pinfunction "2_2") (pintype "passive"))
      (node (ref "TPS61090") (pin "14") (pinfunction "FB_14") (pintype "input"))
    )
    (net (code "51") (name "Net-(TPS61090-LBI)") (class "Default")
      (node (ref "R6") (pin "2") (pinfunction "2_2") (pintype "passive"))
      (node (ref "R7") (pin "1") (pinfunction "1_1") (pintype "passive"))
      (node (ref "TPS61090") (pin "9") (pinfunction "LBI_9") (pintype "input"))
    )
    (net (code "52") (name "Net-(U$2-EN)") (class "Default")
      (node (ref "U$12") (pin "OUT") (pinfunction "OUT_OUT") (pintype "bidirectional"))
      (node (ref "U$2") (pin "3") (pinfunction "EN_3") (pintype "bidirectional"))
    )
    (net (code "53") (name "Net-(U$2-ISET)") (class "Default")
      (node (ref "R1") (pin "1") (pinfunction "1_1") (pintype "passive"))
      (node (ref "U$2") (pin "4") (pinfunction "ISET_4") (pintype "bidirectional"))
    )
    (net (code "54") (name "Net-(U$20-Y0)") (class "Default")
      (node (ref "R18") (pin "1") (pinfunction "1_1") (pintype "passive"))
      (node (ref "U$20") (pin "6") (pinfunction "Y0_6") (pintype "bidirectional"))
      (node (ref "U$22") (pin "1") (pinfunction "S1_1") (pintype "passive"))
    )
    (net (code "55") (name "Net-(U$21-REGOUT)") (class "Default")
      (node (ref "C18") (pin "1") (pinfunction "1_1") (pintype "passive"))
      (node (ref "U$21") (pin "10") (pinfunction "REGOUT_10") (pintype "bidirectional"))
    )
    (net (code "56") (name "VBAT") (class "Default")
      (node (ref "C6") (pin "1") (pinfunction "1_1") (pintype "passive"))
      (node (ref "C9") (pin "1") (pinfunction "1_1") (pintype "passive"))
      (node (ref "L1") (pin "P$1") (pinfunction "1_P$1") (pintype "passive"))
      (node (ref "R13") (pin "1") (pinfunction "1_1") (pintype "passive"))
      (node (ref "R7") (pin "2") (pinfunction "2_2") (pintype "passive"))
      (node (ref "TPS61090") (pin "8") (pinfunction "VBAT_8") (pintype "input"))
      (node (ref "U$2") (pin "5") (pinfunction "VOUT_5") (pintype "bidirectional"))
    )
    (net (code "57") (name "VBUS") (class "Default")
      (node (ref "C4") (pin "1") (pinfunction "1_1") (pintype "passive"))
      (node (ref "CHARGE") (pin "ANODE") (pinfunction "A_ANODE") (pintype "passive"))
      (node (ref "DONE") (pin "ANODE") (pinfunction "A_ANODE") (pintype "passive"))
      (node (ref "FT231XQ") (pin "12") (pinfunction "VCC_12") (pintype "bidirectional"))
      (node (ref "MCP73871") (pin "P$17") (pinfunction "CE_P$17") (pintype "bidirectional"))
      (node (ref "MCP73871") (pin "P$18") (pinfunction "VIN1_P$18") (pintype "bidirectional"))
      (node (ref "MCP73871") (pin "P$19") (pinfunction "VIN2_P$19") (pintype "bidirectional"))
      (node (ref "MCP73871") (pin "P$3") (pinfunction "SEL_P$3") (pintype "bidirectional"))
      (node (ref "MCP73871") (pin "P$4") (pinfunction "PROG2_P$4") (pintype "bidirectional"))
      (node (ref "MCP73871") (pin "P$9") (pinfunction "/TE_P$9") (pintype "bidirectional"))
      (node (ref "R5") (pin "2") (pinfunction "2_2") (pintype "passive"))
      (node (ref "U$1") (pin "VUSB") (pinfunction "VUSB_VUSB") (pintype "bidirectional"))
    )
    (net (code "58") (name "VLIPO") (class "Default")
      (node (ref "C11") (pin "1") (pinfunction "1_1") (pintype "passive"))
      (node (ref "LIPO") (pin "+") (pinfunction "+_+") (pintype "power_in"))
      (node (ref "MCP73871") (pin "P$14") (pinfunction "VBAT1_P$14") (pintype "bidirectional"))
      (node (ref "MCP73871") (pin "P$15") (pinfunction "VBAT2_P$15") (pintype "bidirectional"))
      (node (ref "MCP73871") (pin "P$16") (pinfunction "VBATSENS_P$16") (pintype "bidirectional"))
    )
    (net (code "59") (name "VSHARE") (class "Default")
      (node (ref "C2") (pin "1") (pinfunction "1_1") (pintype "passive"))
      (node (ref "MCP73871") (pin "P$1") (pinfunction "VOUT1_P$1") (pintype "bidirectional"))
      (node (ref "MCP73871") (pin "P$20") (pinfunction "VOUT2_P$20") (pintype "bidirectional"))
      (node (ref "R11") (pin "1") (pinfunction "1_1") (pintype "passive"))
      (node (ref "R25") (pin "2") (pinfunction "2_2") (pintype "passive"))
      (node (ref "U$12") (pin "VCC") (pinfunction "VCC_VCC") (pintype "bidirectional"))
      (node (ref "U$2") (pin "1") (pinfunction "VIN_1") (pintype "bidirectional"))
    )
    (net (code "60") (name "unconnected-(FT231XQ-CBUS0-Pad15)") (class "Default")
      (node (ref "FT231XQ") (pin "15") (pinfunction "CBUS0_15") (pintype "bidirectional"))
    )
    (net (code "61") (name "unconnected-(FT231XQ-CBUS1-Pad14)") (class "Default")
      (node (ref "FT231XQ") (pin "14") (pinfunction "CBUS1_14") (pintype "bidirectional"))
    )
    (net (code "62") (name "unconnected-(FT231XQ-CBUS2-Pad7)") (class "Default")
      (node (ref "FT231XQ") (pin "7") (pinfunction "CBUS2_7") (pintype "bidirectional"))
    )
    (net (code "63") (name "unconnected-(FT231XQ-CBUS3-Pad16)") (class "Default")
      (node (ref "FT231XQ") (pin "16") (pinfunction "CBUS3_16") (pintype "bidirectional"))
    )
    (net (code "64") (name "unconnected-(FT231XQ-~{CTS}-Pad6)") (class "Default")
      (node (ref "FT231XQ") (pin "6") (pinfunction "~{CTS}_6") (pintype "bidirectional"))
    )
    (net (code "65") (name "unconnected-(FT231XQ-~{DCD}-Pad5)") (class "Default")
      (node (ref "FT231XQ") (pin "5") (pinfunction "~{DCD}_5") (pintype "bidirectional"))
    )
    (net (code "66") (name "unconnected-(FT231XQ-~{DSR}-Pad4)") (class "Default")
      (node (ref "FT231XQ") (pin "4") (pinfunction "~{DSR}_4") (pintype "bidirectional"))
    )
    (net (code "67") (name "unconnected-(FT231XQ-~{RI}-Pad2)") (class "Default")
      (node (ref "FT231XQ") (pin "2") (pinfunction "~{RI}_2") (pintype "bidirectional"))
    )
    (net (code "68") (name "unconnected-(MCP73871-{slash}PG-PadP$6)") (class "Default")
      (node (ref "MCP73871") (pin "P$6") (pinfunction "/PG_P$6") (pintype "bidirectional"))
    )
    (net (code "69") (name "unconnected-(TPS61090-LBO-Pad12)") (class "Default")
      (node (ref "TPS61090") (pin "12") (pinfunction "LBO_12") (pintype "output"))
    )
    (net (code "70") (name "unconnected-(U$1-PadID)") (class "Default")
      (node (ref "U$1") (pin "ID") (pinfunction "ID_ID") (pintype "bidirectional"))
    )
    (net (code "71") (name "unconnected-(U$12-Pad_OUT)") (class "Default")
      (node (ref "U$12") (pin "_OUT") (pinfunction "_OUT__OUT") (pintype "bidirectional"))
    )
    (net (code "72") (name "unconnected-(U$14-1-PadP$1)") (class "Default")
      (node (ref "U$14") (pin "P$1") (pinfunction "1_P$1") (pintype "passive"))
    )
    (net (code "73") (name "unconnected-(U$14-2-PadP$2)") (class "Default")
      (node (ref "U$14") (pin "P$2") (pinfunction "2_P$2") (pintype "passive"))
    )
    (net (code "74") (name "unconnected-(U$20-Y1-Pad4)") (class "Default")
      (node (ref "U$20") (pin "4") (pinfunction "Y1_4") (pintype "bidirectional"))
    )
    (net (code "75") (name "unconnected-(U$21-AUX_CL-Pad7)") (class "Default")
      (node (ref "U$21") (pin "7") (pinfunction "AUX_CL_7") (pintype "bidirectional"))
    )
    (net (code "76") (name "unconnected-(U$21-AUX_SDA-Pad21)") (class "Default")
      (node (ref "U$21") (pin "21") (pinfunction "AUX_SDA_21") (pintype "bidirectional"))
    )
    (net (code "77") (name "unconnected-(U$21-INT-Pad12)") (class "Default")
      (node (ref "U$21") (pin "12") (pinfunction "INT_12") (pintype "bidirectional"))
    )
  )
)
